# Power_Management.net
KiCad netlist of a schematic drawn in Altium Designer
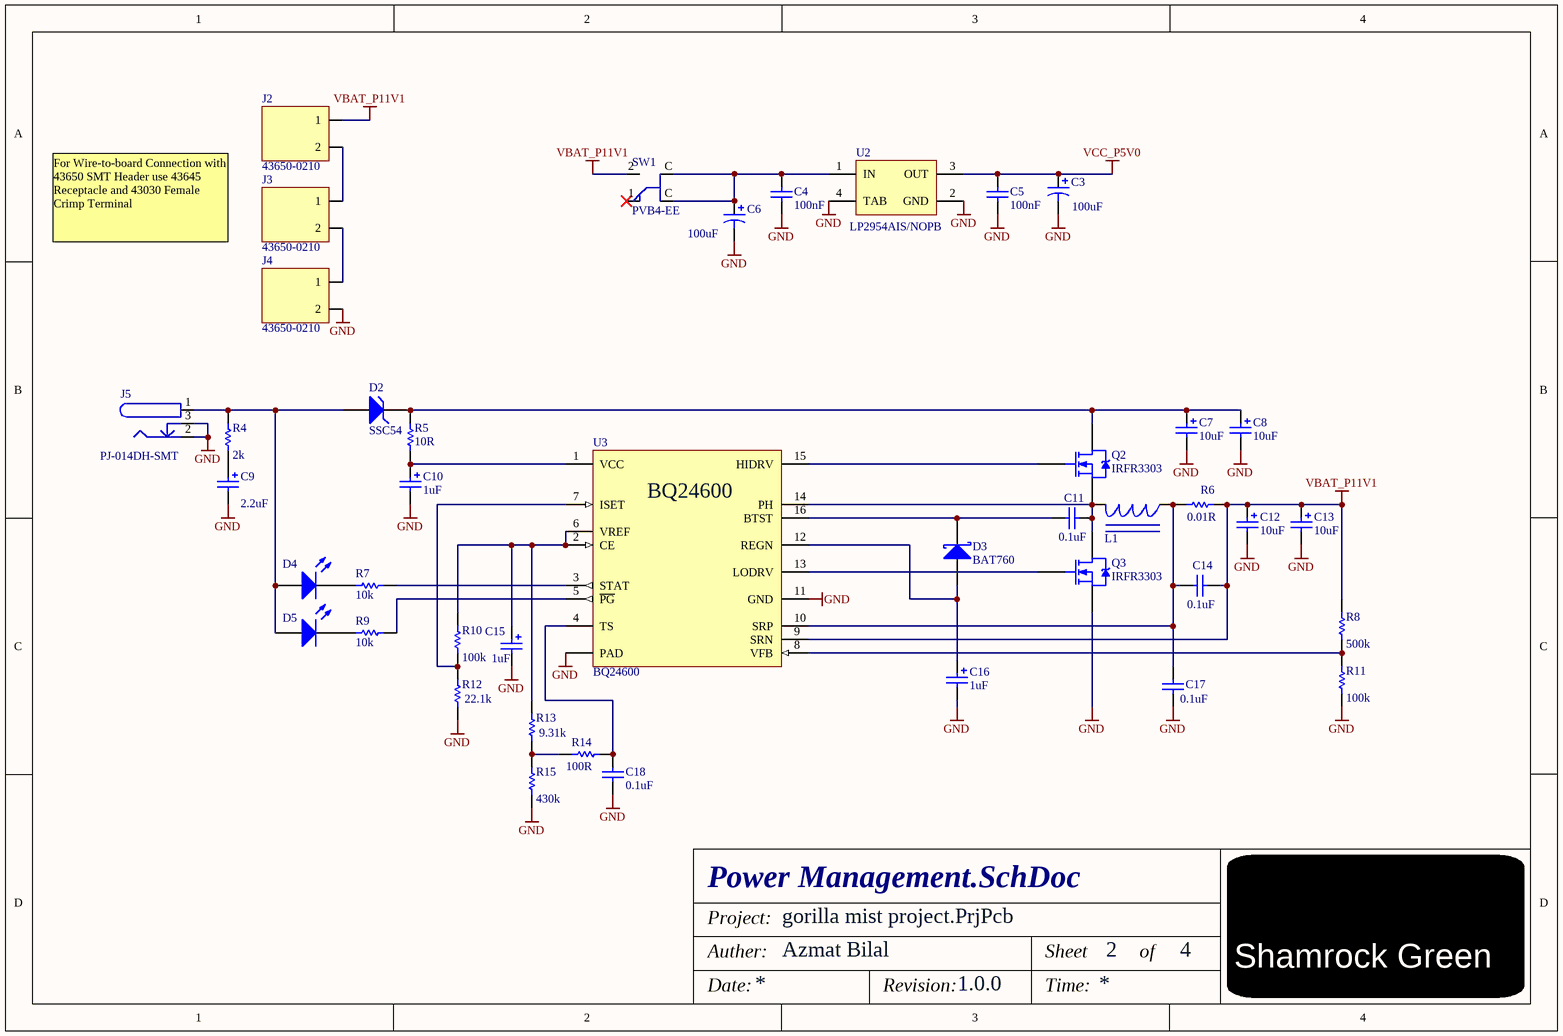
[diagram p0: Power Management.SchDoc]

(export (version "E")
  (design (tool "Eeschema 10.0.6"))
  (components
    (comp (ref "C3")
      (value "100uF")
      (footprint "D")
      (description "Solid Tantalum Chip Capacitor, Standard T491 Series - Industrial Grade")
      (fields (field (name "Comment") "T491D107K016AT") (field (name "PUBLISHER") "Altium Limited"))
      (libsource (lib "KEMET Chip Capacitor") (part "T491D"))
    )
    (comp (ref "C4")
      (value "100nF")
      (footprint "0603")
      (description "Ceramic Chip Capacitor - Standard")
      (fields (field (name "Comment") "C0603C104K3RACTU") (field (name "PUBLISHER") "Altium Limited"))
      (libsource (lib "KEMET Chip Capacitor") (part "C0603"))
    )
    (comp (ref "C5")
      (value "100nF")
      (footprint "0603")
      (description "Ceramic Chip Capacitor - Standard")
      (fields (field (name "Comment") "C0603C104K3RACTU") (field (name "PUBLISHER") "Altium Limited"))
      (libsource (lib "KEMET Chip Capacitor") (part "C0603"))
    )
    (comp (ref "C6")
      (value "100uF")
      (footprint "D")
      (description "Solid Tantalum Chip Capacitor, Standard T491 Series - Industrial Grade")
      (fields (field (name "Comment") "T491D107K016AT") (field (name "PUBLISHER") "Altium Limited"))
      (libsource (lib "KEMET Chip Capacitor") (part "T491D"))
    )
    (comp (ref "C7")
      (value "10uF")
      (footprint "A")
      (description "Solid Tantalum Chip Capacitor, Standard T491 Series - Industrial Grade")
      (fields (field (name "Comment") "T491A106K010AT") (field (name "PUBLISHER") "Altium Limited"))
      (libsource (lib "KEMET Chip Capacitor") (part "T491A"))
    )
    (comp (ref "C8")
      (value "10uF")
      (footprint "A")
      (description "Solid Tantalum Chip Capacitor, Standard T491 Series - Industrial Grade")
      (fields (field (name "Comment") "T491A106K010AT") (field (name "PUBLISHER") "Altium Limited"))
      (libsource (lib "KEMET Chip Capacitor") (part "T491A"))
    )
    (comp (ref "C9")
      (value "2.2uF")
      (footprint "A")
      (description "Solid Tantalum Chip Capacitor, Standard T491 Series - Industrial Grade")
      (fields (field (name "Comment") "T491A225K010AT") (field (name "PUBLISHER") "Altium Limited"))
      (libsource (lib "KEMET Chip Capacitor") (part "T491A"))
    )
    (comp (ref "C10")
      (value "1uF")
      (footprint "M")
      (description "Solid Tantalum Chip Capacitors  298D microtan, 10uF, 6.3V, 20%,  0603,")
      (fields (field (name "Comment") "298D106X06R3M2T"))
      (libsource (lib "Vishay Sprague Tantalum Chip Capacitor") (part "298D106X06R3M2T"))
    )
    (comp (ref "C11")
      (value "0.1uF")
      (footprint "0603")
      (description "Ceramic Chip Capacitor - Standard")
      (fields (field (name "Comment") "C0603C104K4RACTU") (field (name "PUBLISHER") "Altium Limited"))
      (libsource (lib "KEMET Chip Capacitor") (part "C0603"))
    )
    (comp (ref "C12")
      (value "10uF")
      (footprint "A")
      (description "Solid Tantalum Chip Capacitor, Standard T491 Series - Industrial Grade")
      (fields (field (name "Comment") "T491A106K010AT") (field (name "PUBLISHER") "Altium Limited"))
      (libsource (lib "KEMET Chip Capacitor") (part "T491A"))
    )
    (comp (ref "C13")
      (value "10uF")
      (footprint "A")
      (description "Solid Tantalum Chip Capacitor, Standard T491 Series - Industrial Grade")
      (fields (field (name "Comment") "T491A106K010AT") (field (name "PUBLISHER") "Altium Limited"))
      (libsource (lib "KEMET Chip Capacitor") (part "T491A"))
    )
    (comp (ref "C14")
      (value "0.1uF")
      (footprint "0603")
      (description "Ceramic Chip Capacitor - Standard")
      (fields (field (name "Comment") "C0603C104K4RACTU") (field (name "PUBLISHER") "Altium Limited"))
      (libsource (lib "KEMET Chip Capacitor") (part "C0603"))
    )
    (comp (ref "C15")
      (value "1uF")
      (footprint "M")
      (description "Solid Tantalum Chip Capacitors  298D microtan, 10uF, 6.3V, 20%,  0603,")
      (fields (field (name "Comment") "298D106X06R3M2T"))
      (libsource (lib "Vishay Sprague Tantalum Chip Capacitor") (part "298D106X06R3M2T"))
    )
    (comp (ref "C16")
      (value "1uF")
      (footprint "M")
      (description "Solid Tantalum Chip Capacitors  298D microtan, 10uF, 6.3V, 20%,  0603,")
      (fields (field (name "Comment") "298D106X06R3M2T"))
      (libsource (lib "Vishay Sprague Tantalum Chip Capacitor") (part "298D106X06R3M2T"))
    )
    (comp (ref "C17")
      (value "0.1uF")
      (footprint "0603")
      (description "Ceramic Chip Capacitor - Standard")
      (fields (field (name "Comment") "C0603C104K4RACTU") (field (name "PUBLISHER") "Altium Limited"))
      (libsource (lib "KEMET Chip Capacitor") (part "C0603"))
    )
    (comp (ref "C18")
      (value "0.1uF")
      (footprint "0603")
      (description "Ceramic Chip Capacitor - Standard")
      (fields (field (name "Comment") "C0603C104K4RACTU") (field (name "PUBLISHER") "Altium Limited"))
      (libsource (lib "KEMET Chip Capacitor") (part "C0603"))
    )
    (comp (ref "D2")
      (value "SSC54")
      (footprint "DO-214AB (SMC)")
      (description "High Current Density Schottky Rectifier, 5A, 40V, DO-214AB (SMC)")
      (libsource (lib "Vishay Lite-On Discrete Diode") (part "SSC54"))
    )
    (comp (ref "D3")
      (value "BAT760")
      (footprint "SOD323")
      (description "Schottky Barrier Diode")
      (fields (field (name "PUBLISHER") "Altium Limited"))
      (libsource (lib "Philips Discrete Diode - Schottky") (part "BAT760"))
    )
    (comp (ref "D4")
      (value "HSMA-C190")
      (footprint "1.6X0.8X0.8")
      (description "Blue Surface Mount Chip LED, Blue")
      (fields (field (name "PUBLISHER") "Altium Limited"))
      (libsource (lib "Avago Optoelectronic LED") (part "HSMB-C190"))
    )
    (comp (ref "D5")
      (value "HSMG-C190")
      (footprint "1.6X0.8X0.8")
      (description "Blue Surface Mount Chip LED, Blue")
      (fields (field (name "PUBLISHER") "Altium Limited"))
      (libsource (lib "Avago Optoelectronic LED") (part "HSMB-C190"))
    )
    (comp (ref "J2")
      (value "43650-0210")
      (footprint "43650-0210")
      (description "Power Connector, Micro-Fit 3.0 Header, SMT, Single Row, Right Angle, 2 Circuits")
      (libsource (lib "Molex Power Connector") (part "43650-0210"))
    )
    (comp (ref "J3")
      (value "43650-0210")
      (footprint "43650-0210")
      (description "Power Connector, Micro-Fit 3.0 Header, SMT, Single Row, Right Angle, 2 Circuits")
      (libsource (lib "Molex Power Connector") (part "43650-0210"))
    )
    (comp (ref "J4")
      (value "43650-0210")
      (footprint "43650-0210")
      (description "Power Connector, Micro-Fit 3.0 Header, SMT, Single Row, Right Angle, 2 Circuits")
      (libsource (lib "Molex Power Connector") (part "43650-0210"))
    )
    (comp (ref "J5")
      (value "PJ-014DH-SMT")
      (footprint "PJ-014DH-SMT")
      (description "DC Power Jack, 1.3 ID 3.5 OD, 3.5A, 24VDC, Normally Closed Switch, SMT, Right Angle")
      (libsource (lib "CUI Power Jack") (part "PJ-014DH-SMT"))
    )
    (comp (ref "L1")
      (value "IHLP2525CZERxRxM11")
      (footprint "IHLP")
      (description "Low Profile, High Current IHLP Inductor, 1uH to 22uH, 2.5 to 9A saturation current")
      (libsource (lib "Vishay Dale Inductor") (part "IHLP2525CZ"))
    )
    (comp (ref "Q2")
      (value "IRFR3303")
      (footprint "TO-252AA_N")
      (description "HEXFET Power MOSFET")
      (fields (field (name "PUBLISHER") "Altium Limited"))
      (libsource (lib "IR Discrete MOSFET - Power") (part "IRFR3303"))
    )
    (comp (ref "Q3")
      (value "IRFR3303")
      (footprint "TO-252AA_N")
      (description "HEXFET Power MOSFET")
      (fields (field (name "PUBLISHER") "Altium Limited"))
      (libsource (lib "IR Discrete MOSFET - Power") (part "IRFR3303"))
    )
    (comp (ref "R4")
      (value "2k")
      (footprint "3-0603")
      (fields (field (name "Comment") "ERJ3EKF2001V") (field (name "PUBLISHER") "Altium Limited"))
      (libsource (lib "Panasonic Resistor") (part "ERJ3EK"))
    )
    (comp (ref "R5")
      (value "10R")
      (footprint "8-1206")
      (description "Precision Thick Film Chip Resistor, 10 Ohm to 2.2M Ohm Range, 1% Tolerance, 1206 Size, 0.125 W")
      (fields (field (name "Comment") "ERJ-8ENF10R0V") (field (name "PUBLISHER") "Altium Limited"))
      (libsource (lib "Panasonic Resistor") (part "ERJ8EN"))
    )
    (comp (ref "R6")
      (value "0.01R")
      (footprint "M1WS-2512")
      (description "Low Resistance Value Chip Resistor, 3m Ohm to 20m Ohm Range, 1% and 5% Tolerance, 2512 Size, 1 W")
      (fields (field (name "Comment") "ERJM1WSF10MU") (field (name "PUBLISHER") "Altium Limited"))
      (libsource (lib "Panasonic Resistor") (part "ERJM1WS"))
    )
    (comp (ref "R7")
      (value "10k")
      (footprint "3-0603")
      (description "Thick Film Chip Resistor, 1 Ohm to 10M Ohm Range, 5% Tolerance, 0603 Size, 0.1 W")
      (fields (field (name "Comment") "ERJ3GEYJ103V") (field (name "PUBLISHER") "Altium Limited"))
      (libsource (lib "Panasonic Resistor") (part "ERJ3GE"))
    )
    (comp (ref "R8")
      (value "500k")
      (footprint "3-0603")
      (description "Thick Film Chip Resistor, 1 Ohm to 10M Ohm Range, 5% Tolerance, 0603 Size, 0.1 W")
      (fields (field (name "Comment") "ERJ3GEYJ514V") (field (name "PUBLISHER") "Altium Limited"))
      (libsource (lib "Panasonic Resistor") (part "ERJ3GE"))
    )
    (comp (ref "R9")
      (value "10k")
      (footprint "3-0603")
      (description "Thick Film Chip Resistor, 1 Ohm to 10M Ohm Range, 5% Tolerance, 0603 Size, 0.1 W")
      (fields (field (name "Comment") "ERJ3GEYJ103V") (field (name "PUBLISHER") "Altium Limited"))
      (libsource (lib "Panasonic Resistor") (part "ERJ3GE"))
    )
    (comp (ref "R10")
      (value "100k")
      (footprint "3-0603")
      (description "Thick Film Chip Resistor, 1 Ohm to 10M Ohm Range, 5% Tolerance, 0603 Size, 0.1 W")
      (fields (field (name "Comment") "ERJ-3GEYJ104V") (field (name "PUBLISHER") "Altium Limited"))
      (libsource (lib "Panasonic Resistor") (part "ERJ3GE"))
    )
    (comp (ref "R11")
      (value "100k")
      (footprint "3-0603")
      (description "Thick Film Chip Resistor, 1 Ohm to 10M Ohm Range, 5% Tolerance, 0603 Size, 0.1 W")
      (fields (field (name "Comment") "ERJ-3GEYJ104V") (field (name "PUBLISHER") "Altium Limited"))
      (libsource (lib "Panasonic Resistor") (part "ERJ3GE"))
    )
    (comp (ref "R12")
      (value "22.1k")
      (footprint "3-0603")
      (fields (field (name "Comment") "ERJ3EKF2212V") (field (name "PUBLISHER") "Altium Limited"))
      (libsource (lib "Panasonic Resistor") (part "ERJ3EK"))
    )
    (comp (ref "R13")
      (value "9.31k")
      (footprint "3-0603")
      (fields (field (name "Comment") "ERJ3EKF9311V") (field (name "PUBLISHER") "Altium Limited"))
      (libsource (lib "Panasonic Resistor") (part "ERJ3EK"))
    )
    (comp (ref "R14")
      (value "100R")
      (footprint "3-0603")
      (description "Thick Film Chip Resistor, 1 Ohm to 10M Ohm Range, 5% Tolerance, 0603 Size, 0.1 W")
      (fields (field (name "Comment") "ERJ3GEYJ101V") (field (name "PUBLISHER") "Altium Limited"))
      (libsource (lib "Panasonic Resistor") (part "ERJ3GE"))
    )
    (comp (ref "R15")
      (value "430k")
      (footprint "3-0603")
      (description "Thick Film Chip Resistor, 1 Ohm to 10M Ohm Range, 5% Tolerance, 0603 Size, 0.1 W")
      (fields (field (name "Comment") "ERJ3GEYJ434V") (field (name "PUBLISHER") "Altium Limited"))
      (libsource (lib "Panasonic Resistor") (part "ERJ3GE"))
    )
    (comp (ref "SW1")
      (value "PVB4-EE")
      (footprint "PVB4-EE")
      (description "Low profile SPDT switch, SMD.")
      (libsource (lib "CK Switch") (part "PVB4-EE300NSLFS"))
    )
    (comp (ref "U2")
      (value "LP2954AIS/NOPB")
      (footprint "TS3B_N")
      (description "5V Micropower Low-Dropout Voltage Regulator, 3-pin TO-263, Pb-Free")
      (fields
        (field (name "MANUFACTURER") "National Semiconductor")
        (field (name "PUBLISHER") "Altium Limited")
      )
      (libsource (lib "NSC LDO") (part "LP2954AIS/NOPB"))
    )
    (comp (ref "U3")
      (value "BQ24600")
      (footprint "QFN16")
      (description "Multi-cell Battery Charger IC, Lithium ion and Lithium Polymer, standalone.")
      (libsource (lib "TI Power Mgt Power Controller") (part "BQ24600"))
    )
  )
  (nets
    (net (code "1") (name "GND") (class "Default")
      (node (ref "C10") (pin "2") (pinfunction "2_2") (pintype "passive"))
      (node (ref "C12") (pin "2") (pinfunction "2_2") (pintype "passive"))
      (node (ref "C13") (pin "2") (pinfunction "2_2") (pintype "passive"))
      (node (ref "C15") (pin "2") (pinfunction "2_2") (pintype "passive"))
      (node (ref "C16") (pin "2") (pinfunction "2_2") (pintype "passive"))
      (node (ref "C17") (pin "1") (pinfunction "1_1") (pintype "passive"))
      (node (ref "C18") (pin "1") (pinfunction "1_1") (pintype "passive"))
      (node (ref "C3") (pin "2") (pinfunction "2_2") (pintype "passive"))
      (node (ref "C4") (pin "1") (pinfunction "1_1") (pintype "passive"))
      (node (ref "C5") (pin "1") (pinfunction "1_1") (pintype "passive"))
      (node (ref "C6") (pin "2") (pinfunction "2_2") (pintype "passive"))
      (node (ref "C7") (pin "2") (pinfunction "2_2") (pintype "passive"))
      (node (ref "C8") (pin "2") (pinfunction "2_2") (pintype "passive"))
      (node (ref "C9") (pin "2") (pinfunction "2_2") (pintype "passive"))
      (node (ref "J4") (pin "2") (pinfunction "2_2") (pintype "power_in"))
      (node (ref "J5") (pin "2") (pinfunction "2_2") (pintype "power_in"))
      (node (ref "J5") (pin "3") (pinfunction "3_3") (pintype "power_in"))
      (node (ref "Q3") (pin "3") (pinfunction "S_3") (pintype "passive"))
      (node (ref "R11") (pin "1") (pinfunction "1_1") (pintype "passive"))
      (node (ref "R12") (pin "1") (pinfunction "1_1") (pintype "passive"))
      (node (ref "R15") (pin "1") (pinfunction "1_1") (pintype "passive"))
      (node (ref "U2") (pin "2") (pinfunction "GND_2") (pintype "power_in"))
      (node (ref "U2") (pin "4") (pinfunction "TAB_4") (pintype "power_in"))
      (node (ref "U3") (pin "11") (pinfunction "GND_11") (pintype "power_in"))
      (node (ref "U3") (pin "17") (pinfunction "PAD_17") (pintype "power_in"))
    )
    (net (code "2") (name "Net-(C9-Pad1)") (class "Default")
      (node (ref "C9") (pin "1") (pinfunction "1_1") (pintype "passive"))
      (node (ref "R4") (pin "1") (pinfunction "1_1") (pintype "passive"))
    )
    (net (code "3") (name "Net-(D2-A)") (class "Default")
      (node (ref "D2") (pin "1") (pinfunction "A_1") (pintype "passive"))
      (node (ref "D4") (pin "1") (pinfunction "A_1") (pintype "passive"))
      (node (ref "D5") (pin "1") (pinfunction "A_1") (pintype "passive"))
      (node (ref "J5") (pin "1") (pinfunction "1_1") (pintype "power_in"))
      (node (ref "R4") (pin "2") (pinfunction "2_2") (pintype "passive"))
    )
    (net (code "4") (name "Net-(D2-K)") (class "Default")
      (node (ref "C7") (pin "1") (pinfunction "1_1") (pintype "passive"))
      (node (ref "C8") (pin "1") (pinfunction "1_1") (pintype "passive"))
      (node (ref "D2") (pin "2") (pinfunction "K_2") (pintype "passive"))
      (node (ref "Q2") (pin "4") (pinfunction "D_4") (pintype "passive"))
      (node (ref "R5") (pin "1") (pinfunction "1_1") (pintype "passive"))
    )
    (net (code "5") (name "Net-(D3-A)") (class "Default")
      (node (ref "C16") (pin "1") (pinfunction "1_1") (pintype "passive"))
      (node (ref "D3") (pin "2") (pinfunction "A_2") (pintype "passive"))
      (node (ref "U3") (pin "12") (pinfunction "REGN_12") (pintype "power_in"))
    )
    (net (code "6") (name "Net-(D3-K)") (class "Default")
      (node (ref "C11") (pin "1") (pinfunction "1_1") (pintype "passive"))
      (node (ref "D3") (pin "1") (pinfunction "K_1") (pintype "passive"))
      (node (ref "U3") (pin "16") (pinfunction "BTST_16") (pintype "power_in"))
    )
    (net (code "7") (name "Net-(D4-K)") (class "Default")
      (node (ref "D4") (pin "2") (pinfunction "K_2") (pintype "passive"))
      (node (ref "R7") (pin "2") (pinfunction "2_2") (pintype "passive"))
    )
    (net (code "8") (name "Net-(D5-K)") (class "Default")
      (node (ref "D5") (pin "2") (pinfunction "K_2") (pintype "passive"))
      (node (ref "R9") (pin "2") (pinfunction "2_2") (pintype "passive"))
    )
    (net (code "9") (name "Net-(J2-Pad2)") (class "Default")
      (node (ref "J2") (pin "2") (pinfunction "2_2") (pintype "power_in"))
      (node (ref "J3") (pin "1") (pinfunction "1_1") (pintype "power_in"))
    )
    (net (code "10") (name "Net-(J3-Pad2)") (class "Default")
      (node (ref "J3") (pin "2") (pinfunction "2_2") (pintype "power_in"))
      (node (ref "J4") (pin "1") (pinfunction "1_1") (pintype "power_in"))
    )
    (net (code "11") (name "Net-(Q2-G)") (class "Default")
      (node (ref "Q2") (pin "1") (pinfunction "G_1") (pintype "passive"))
      (node (ref "U3") (pin "15") (pinfunction "HIDRV_15") (pintype "power_in"))
    )
    (net (code "12") (name "Net-(Q2-S)") (class "Default")
      (node (ref "C11") (pin "2") (pinfunction "2_2") (pintype "passive"))
      (node (ref "L1") (pin "2") (pinfunction "2_2") (pintype "power_in"))
      (node (ref "Q2") (pin "3") (pinfunction "S_3") (pintype "passive"))
      (node (ref "Q3") (pin "4") (pinfunction "D_4") (pintype "passive"))
      (node (ref "U3") (pin "14") (pinfunction "PH_14") (pintype "power_in"))
    )
    (net (code "13") (name "Net-(Q3-G)") (class "Default")
      (node (ref "Q3") (pin "1") (pinfunction "G_1") (pintype "passive"))
      (node (ref "U3") (pin "13") (pinfunction "LODRV_13") (pintype "power_in"))
    )
    (net (code "14") (name "Net-(R13-Pad1)") (class "Default")
      (node (ref "R13") (pin "1") (pinfunction "1_1") (pintype "passive"))
      (node (ref "R14") (pin "1") (pinfunction "1_1") (pintype "passive"))
      (node (ref "R15") (pin "2") (pinfunction "2_2") (pintype "passive"))
    )
    (net (code "15") (name "Net-(U2-IN)") (class "Default")
      (node (ref "C4") (pin "2") (pinfunction "2_2") (pintype "passive"))
      (node (ref "C6") (pin "1") (pinfunction "1_1") (pintype "passive"))
      (node (ref "SW1") (pin "C") (pinfunction "C_C") (pintype "passive"))
      (node (ref "U2") (pin "1") (pinfunction "IN_1") (pintype "power_in"))
    )
    (net (code "16") (name "Net-(U3-CE)") (class "Default")
      (node (ref "C15") (pin "1") (pinfunction "1_1") (pintype "passive"))
      (node (ref "R10") (pin "2") (pinfunction "2_2") (pintype "passive"))
      (node (ref "R13") (pin "2") (pinfunction "2_2") (pintype "passive"))
      (node (ref "U3") (pin "2") (pinfunction "CE_2") (pintype "input"))
      (node (ref "U3") (pin "6") (pinfunction "VREF_6") (pintype "power_in"))
    )
    (net (code "17") (name "Net-(U3-ISET)") (class "Default")
      (node (ref "R10") (pin "1") (pinfunction "1_1") (pintype "passive"))
      (node (ref "R12") (pin "2") (pinfunction "2_2") (pintype "passive"))
      (node (ref "U3") (pin "7") (pinfunction "ISET_7") (pintype "input"))
    )
    (net (code "18") (name "Net-(U3-SRP)") (class "Default")
      (node (ref "C14") (pin "1") (pinfunction "1_1") (pintype "passive"))
      (node (ref "C17") (pin "2") (pinfunction "2_2") (pintype "passive"))
      (node (ref "L1") (pin "1") (pinfunction "1_1") (pintype "power_in"))
      (node (ref "R6") (pin "1") (pinfunction "1_1") (pintype "passive"))
      (node (ref "U3") (pin "10") (pinfunction "SRP_10") (pintype "passive"))
    )
    (net (code "19") (name "Net-(U3-STAT)") (class "Default")
      (node (ref "R7") (pin "1") (pinfunction "1_1") (pintype "passive"))
      (node (ref "U3") (pin "3") (pinfunction "STAT_3") (pintype "output"))
    )
    (net (code "20") (name "Net-(U3-TS)") (class "Default")
      (node (ref "C18") (pin "2") (pinfunction "2_2") (pintype "passive"))
      (node (ref "R14") (pin "2") (pinfunction "2_2") (pintype "passive"))
      (node (ref "U3") (pin "4") (pinfunction "TS_4") (pintype "passive"))
    )
    (net (code "21") (name "Net-(U3-VCC)") (class "Default")
      (node (ref "C10") (pin "1") (pinfunction "1_1") (pintype "passive"))
      (node (ref "R5") (pin "2") (pinfunction "2_2") (pintype "passive"))
      (node (ref "U3") (pin "1") (pinfunction "VCC_1") (pintype "power_in"))
    )
    (net (code "22") (name "Net-(U3-VFB)") (class "Default")
      (node (ref "R11") (pin "2") (pinfunction "2_2") (pintype "passive"))
      (node (ref "R8") (pin "1") (pinfunction "1_1") (pintype "passive"))
      (node (ref "U3") (pin "8") (pinfunction "VFB_8") (pintype "input"))
    )
    (net (code "23") (name "Net-(U3-~{PG})") (class "Default")
      (node (ref "R9") (pin "1") (pinfunction "1_1") (pintype "passive"))
      (node (ref "U3") (pin "5") (pinfunction "~{PG}_5") (pintype "output"))
    )
    (net (code "24") (name "VBAT_P11V1") (class "Default")
      (node (ref "C12") (pin "1") (pinfunction "1_1") (pintype "passive"))
      (node (ref "C13") (pin "1") (pinfunction "1_1") (pintype "passive"))
      (node (ref "C14") (pin "2") (pinfunction "2_2") (pintype "passive"))
      (node (ref "J2") (pin "1") (pinfunction "1_1") (pintype "power_in"))
      (node (ref "R6") (pin "2") (pinfunction "2_2") (pintype "passive"))
      (node (ref "R8") (pin "2") (pinfunction "2_2") (pintype "passive"))
      (node (ref "SW1") (pin "2") (pinfunction "2_2") (pintype "passive"))
      (node (ref "U3") (pin "9") (pinfunction "SRN_9") (pintype "passive"))
    )
    (net (code "25") (name "VCC_P5V0") (class "Default")
      (node (ref "C3") (pin "1") (pinfunction "1_1") (pintype "passive"))
      (node (ref "C5") (pin "2") (pinfunction "2_2") (pintype "passive"))
      (node (ref "U2") (pin "3") (pinfunction "OUT_3") (pintype "power_in"))
    )
    (net (code "26") (name "unconnected-(SW1-Pad1)") (class "Default")
      (node (ref "SW1") (pin "1") (pinfunction "1_1") (pintype "passive+no_connect"))
    )
  )
)
